# Arduino_Nano.net
KiCad netlist of a schematic drawn in Altium Designer
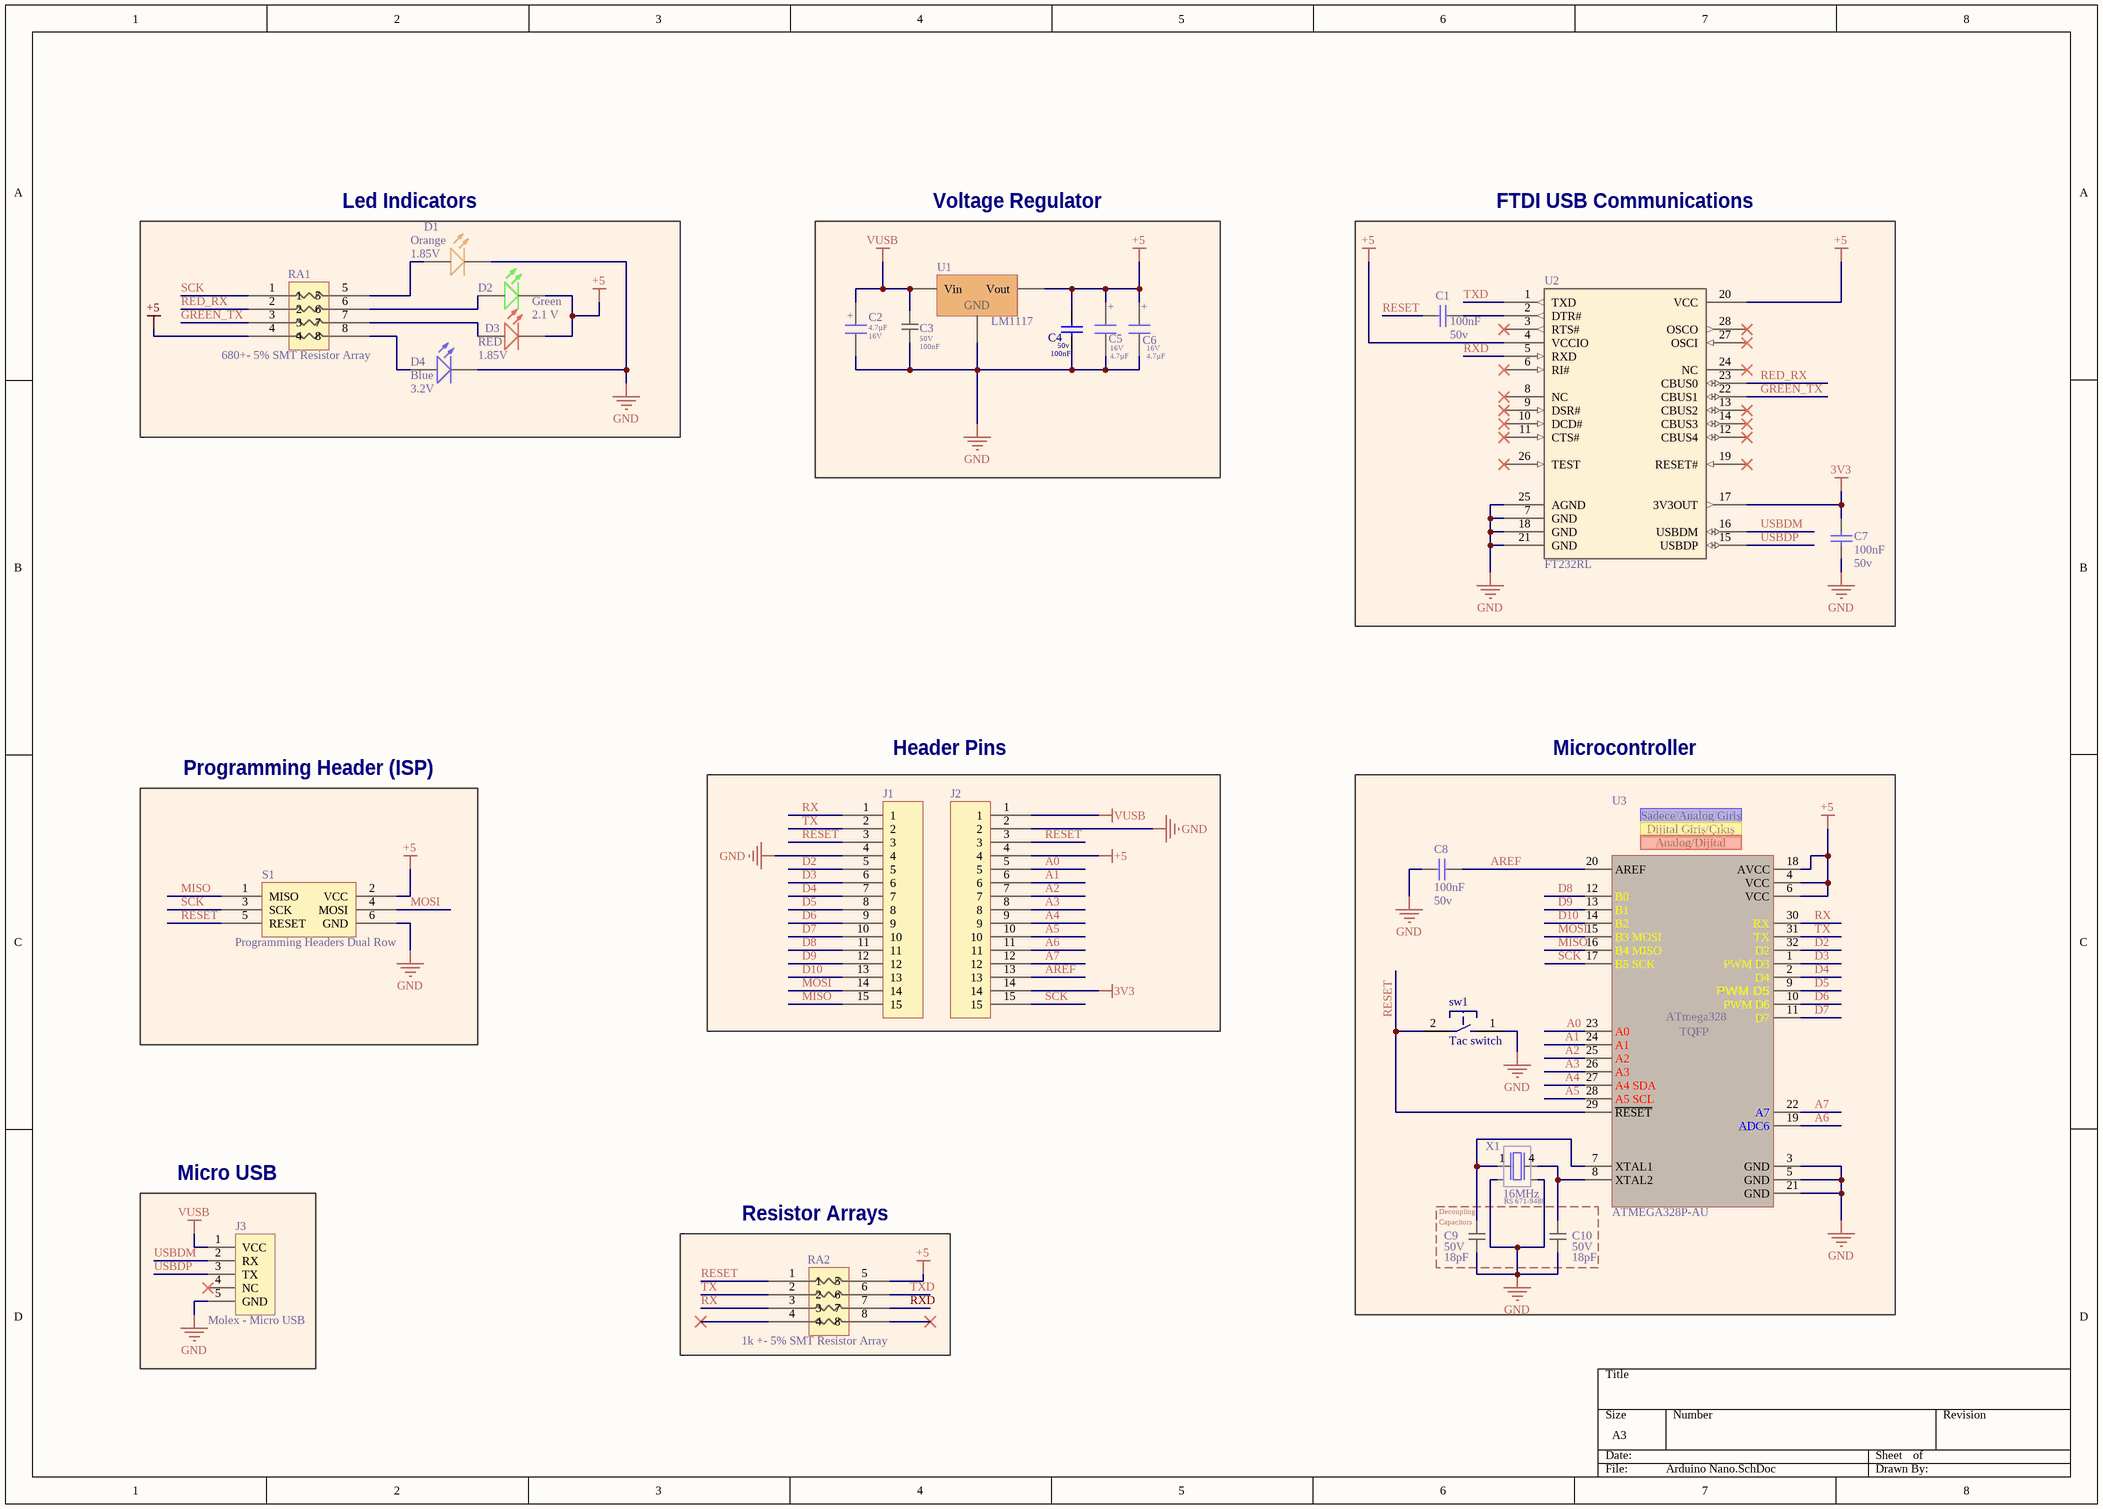
[diagram p0: Arduino Nano.SchDoc]

(export (version "E")
  (design (tool "Eeschema 10.0.6"))
  (components
    (comp (ref "C1")
      (value "100nF")
      (footprint "MY_0805")
      (description "None polar capacitor")
      (fields (field (name "ASID PART NUMBER") "C-AS") (field (name "VOLTE") "50v"))
      (libsource (lib "Kütüphanem") (part "Cap ceramic"))
    )
    (comp (ref "C2")
      (value "4.7µF")
      (footprint "CASE A - 3216X18")
      (description "Capacitor,tantalum,SMT,16V,4.7uF,10%,A-case")
      (fields
        (field (name "TOLERANCE") "10%")
        (field (name "VOLTAGE") "16V")
        (field (name "Comment") "Capacitor SMT Tantalum")
        (field (name "PUBLISHER") "DPSS")
      )
      (libsource (lib "Kütüphanem") (part "4.7µF Tant RS 496-3545"))
    )
    (comp (ref "C3")
      (value "100nF Ceramic Multilayer Capacitor_1")
      (footprint "CAPCP2012X09N")
      (description "AVX 0805 Standard 100nF Ceramic Multilayer Capacitor, 50 V dc X7R Dielectric ±10% SMD")
      (fields
        (field (name "MANUFACTURER") "AVX")
        (field (name "VOLTAGE") "50V")
        (field (name "CAPACITANCE") "100nF")
        (field (name "CREATOR") "Ritesh Kanjee")
      )
      (libsource (lib "Kütüphanem") (part "100nF Ceramic Multilayer Capacitor_1"))
    )
    (comp (ref "C4")
      (value "100nF")
      (footprint "MY_0805")
      (description "None polar capacitor")
      (fields (field (name "ASID PART NUMBER") "C-AS") (field (name "VOLTE") "50v"))
      (libsource (lib "Kütüphanem") (part "Cap ceramic"))
    )
    (comp (ref "C5")
      (value "4.7µF")
      (footprint "CASE A - 3216X18")
      (description "Capacitor,tantalum,SMT,16V,4.7uF,10%,A-case")
      (fields
        (field (name "TOLERANCE") "10%")
        (field (name "VOLTAGE") "16V")
        (field (name "Comment") "Capacitor SMT Tantalum")
        (field (name "PUBLISHER") "DPSS")
      )
      (libsource (lib "Kütüphanem") (part "4.7µF Tant RS 496-3545"))
    )
    (comp (ref "C6")
      (value "4.7µF")
      (footprint "CASE A - 3216X18")
      (description "Capacitor,tantalum,SMT,16V,4.7uF,10%,A-case")
      (fields
        (field (name "TOLERANCE") "10%")
        (field (name "VOLTAGE") "16V")
        (field (name "Comment") "Capacitor SMT Tantalum")
        (field (name "PUBLISHER") "DPSS")
      )
      (libsource (lib "Kütüphanem") (part "4.7µF Tant RS 496-3545"))
    )
    (comp (ref "C7")
      (value "100nF")
      (footprint "MY_0805")
      (description "None polar capacitor")
      (fields (field (name "ASID PART NUMBER") "C-AS") (field (name "VOLTE") "50v"))
      (libsource (lib "Kütüphanem") (part "Cap ceramic"))
    )
    (comp (ref "C8")
      (value "100nF")
      (footprint "MY_0805")
      (description "None polar capacitor")
      (fields (field (name "ASID PART NUMBER") "C-AS") (field (name "VOLTE") "50v"))
      (libsource (lib "Kütüphanem") (part "Cap ceramic"))
    )
    (comp (ref "C9")
      (value "C0805C180J5GACTU")
      (footprint "CAPCP2012X09N")
      (description "18pF Ceramic Multilayer Capacitor, 50 V dc C0G Dielectric ±5% SMD")
      (fields
        (field (name "MANUFACTURER") "Kemet")
        (field (name "VOLTAGE") "50V")
        (field (name "CAPACITANCE") "18pF")
        (field (name "CREATOR") "Ayberk Özkan")
      )
      (libsource (lib "Kütüphanem") (part "18pF Ceramic Multilayer Capacitor, 50 V dc C0G Dielectric ±5% SMD"))
    )
    (comp (ref "C10")
      (value "C0805C180J5GACTU")
      (footprint "CAPCP2012X09N")
      (description "18pF Ceramic Multilayer Capacitor, 50 V dc C0G Dielectric ±5% SMD")
      (fields
        (field (name "MANUFACTURER") "Kemet")
        (field (name "VOLTAGE") "50V")
        (field (name "CAPACITANCE") "18pF")
        (field (name "CREATOR") "Ayberk Özkan")
      )
      (libsource (lib "Kütüphanem") (part "18pF Ceramic Multilayer Capacitor, 50 V dc C0G Dielectric ±5% SMD"))
    )
    (comp (ref "D1")
      (value "Kingbright Orange LED, 200 mcd 120 ° 0805")
      (footprint "LED1913X12NYEL/ORANGE")
      (fields
        (field (name "MANUFACTURER") "KingBright")
        (field (name "MANUFACTURER PART NO.") "KP-2012SEC")
        (field (name "COLOR") "Orange")
        (field (name "FORWARD VOLTAGE") "1.85V")
        (field (name "CREATOR") "Ayberk Özkan")
      )
      (libsource (lib "Kütüphanem") (part "Kingbright Orange LED, 200 mcd 120 ° 0805"))
    )
    (comp (ref "D2")
      (value "Kingbright Green LED, 70 mcd 120 ° 0805")
      (footprint "LED1913X12NGREEN")
      (fields
        (field (name "MANUFACTURER") "KingBright")
        (field (name "MANUFACTURER PART NO.") "KP-2012MGC")
        (field (name "COLOR") "Green")
        (field (name "FORWARD VOLTAGE") "2.1 V")
        (field (name "CREATOR") "Ayberk Özkan")
      )
      (libsource (lib "Kütüphanem") (part "Kingbright Green LED, 70 mcd 120 ° 0805"))
    )
    (comp (ref "D3")
      (value "Kingbright Red LED, 100 mcd 120 ° 0805")
      (footprint "LED1913X12NRED")
      (fields
        (field (name "MANUFACTURER") "KingBright")
        (field (name "MANUFACTURER PART NO.") "KP-2012SRC-PRV")
        (field (name "COLOR") "RED")
        (field (name "FORWARD VOLTAGE") "1.85V")
        (field (name "CREATOR") "Ayberk Özkan")
      )
      (libsource (lib "Kütüphanem") (part "Kingbright Red LED, 100 mcd 120 ° 0805"))
    )
    (comp (ref "D4")
      (value "Kingbright Blue LED, 60 mcd 120 ° 0805")
      (footprint "LED1913X12NBLUE")
      (fields
        (field (name "MANUFACTURER") "KingBright")
        (field (name "MANUFACTURER PART NO.") "KP-2012PBC-A")
        (field (name "COLOR") "Blue")
        (field (name "FORWARD VOLTAGE") "3.2V")
        (field (name "CREATOR") "Ayberk Özkan")
      )
      (libsource (lib "Kütüphanem") (part "Kingbright Blue LED, 60 mcd 120 ° 0805"))
    )
    (comp (ref "J1")
      (value "connector;str header;single row;.1 cont centers;.095 tail;gold or gtx;36 contact")
      (footprint "Header")
      (fields
        (field (name "MANUFACTURER") "FCI")
        (field (name "MANUFACTURER PART NO.") "68000-236HLF")
        (field (name "CREATED BY") "Ayberk Özkan")
      )
      (libsource (lib "") (part "Single row; PCB headers_1"))
    )
    (comp (ref "J2")
      (value "connector;str header;single row;.1 cont centers;.095 tail;gold or gtx;36 contact")
      (footprint "Header")
      (fields
        (field (name "MANUFACTURER") "FCI")
        (field (name "MANUFACTURER PART NO.") "68000-236HLF")
        (field (name "CREATED BY") "Ayberk Özkan")
      )
      (libsource (lib "Kütüphanem") (part "Single row; PCB headers"))
    )
    (comp (ref "J3")
      (value "Molex - Micro USB")
      (footprint "MOLEX_1050170001")
      (description "Molex USB Connector, SMT, Socket B, Solder, Right Angle")
      (libsource (lib "Kütüphanem") (part "Molex - Micro USB Connector 30V, 1.8A"))
    )
    (comp (ref "RA1")
      (value "680+- 5% SMT Resistor Array")
      (footprint "1206 RA")
      (description "680 +- 5% SMT Resistor Array 4 Res 1206")
      (fields
        (field (name "MANUFACTURER") "Bourns")
        (field (name "MANUFACTURER PART NO.") "CAY16-681J4LF")
        (field (name "CREATOR") "Ayberk Özkan")
      )
      (libsource (lib "Kütüphanem") (part "680 +- 5% SMT Resistor Array 4 Res 1206"))
    )
    (comp (ref "RA2")
      (value "1k +- 5% SMT Resistor Array")
      (footprint "1206 RA")
      (description "1k +- 5% SMT Resistor Array 4 Res")
      (fields
        (field (name "MANUFACTURER") "Bourns")
        (field (name "MANUFACTURER PART NO.") "CAY16-102J4LF")
        (field (name "CREATOR") "Ayberk Özkan")
      )
      (libsource (lib "Kütüphanem") (part "1k +- 5% SMT Resistor Array"))
    )
    (comp (ref "S1")
      (value "Programming Headers Dual Row")
      (footprint "ISP HEADER")
      (libsource (lib "Kütüphanem") (part "Programming ISP, Programming Headers Dual Row"))
    )
    (comp (ref "sw1")
      (value "Tac switch")
      (footprint "MY_PB-SMD")
      (description "small tac switch")
      (fields (field (name "ASID PART NUMBER") "Tac switch-AS"))
      (libsource (lib "Kütüphanem") (part "Tac switch_1"))
    )
    (comp (ref "U1")
      (value "LM1117")
      (footprint "MY_SOT223")
      (description "Low Drop Voltage Reg")
      (fields (field (name "ASID PART NUMBER") "LM1117-AS"))
      (libsource (lib "Kütüphanem") (part "LM1117"))
    )
    (comp (ref "U2")
      (value "FT232RL")
      (footprint "SSOP-28-FT232RL")
      (description "USB Bridge, USB to UART USB 2.0 UART Interface 28-SSOP")
      (libsource (lib "Kütüphanem") (part "FT232RL"))
    )
    (comp (ref "U3")
      (value "ATMEGA328P-AU")
      (footprint "TQFP80P900X900X120-32N")
      (description "ATmega48A/PA/88A/PA/168A/PA/328/P")
      (fields (field (name "CREATED BY") "Ayberk"))
      (libsource (lib "Kütüphanem") (part "AtmelMicrocontroller"))
    )
    (comp (ref "X1")
      (value "16MHz")
      (footprint "Aker S5C Crystal")
      (description "Aker S5C SMT Crystal")
      (fields
        (field (name "MANUFACTURER") "Aker")
        (field (name "MANUFACTURER PART #") "C5S-16.000-12-3030-X")
        (field (name "RS") "RS 671-9488")
        (field (name "CREATOR") "Ayberk Özkan")
      )
      (libsource (lib "Kütüphanem") (part "Aker  C5S-16.000-12-3030-X"))
    )
  )
  (nets
    (net (code "1") (name "+5") (class "Default")
      (node (ref "C4") (pin "2") (pinfunction "2_2") (pintype "passive"))
      (node (ref "C5") (pin "1") (pinfunction "1_1") (pintype "passive"))
      (node (ref "C6") (pin "1") (pinfunction "1_1") (pintype "passive"))
      (node (ref "D2") (pin "2") (pinfunction "K_2") (pintype "passive"))
      (node (ref "D3") (pin "2") (pinfunction "K_2") (pintype "passive"))
      (node (ref "J2") (pin "4") (pinfunction "4_4") (pintype "passive"))
      (node (ref "RA1") (pin "4") (pinfunction "4_4") (pintype "passive"))
      (node (ref "RA2") (pin "5") (pinfunction "5_5") (pintype "passive"))
      (node (ref "S1") (pin "2") (pinfunction "VCC_2") (pintype "passive"))
      (node (ref "U1") (pin "2") (pinfunction "Vout_2") (pintype "passive"))
      (node (ref "U2") (pin "20") (pinfunction "VCC_20") (pintype "power_in"))
      (node (ref "U2") (pin "4") (pinfunction "VCCIO_4") (pintype "power_in"))
      (node (ref "U3") (pin "18") (pinfunction "AVCC_18") (pintype "passive"))
      (node (ref "U3") (pin "4") (pinfunction "VCC_4") (pintype "passive"))
      (node (ref "U3") (pin "6") (pinfunction "VCC_6") (pintype "passive"))
    )
    (net (code "2") (name "/A0") (class "Default")
      (node (ref "J2") (pin "5") (pinfunction "5_5") (pintype "passive"))
      (node (ref "U3") (pin "23") (pinfunction "A0_23") (pintype "passive"))
    )
    (net (code "3") (name "/A1") (class "Default")
      (node (ref "J2") (pin "6") (pinfunction "6_6") (pintype "passive"))
      (node (ref "U3") (pin "24") (pinfunction "A1_24") (pintype "passive"))
    )
    (net (code "4") (name "/A2") (class "Default")
      (node (ref "J2") (pin "7") (pinfunction "7_7") (pintype "passive"))
      (node (ref "U3") (pin "25") (pinfunction "A2_25") (pintype "passive"))
    )
    (net (code "5") (name "/A3") (class "Default")
      (node (ref "J2") (pin "8") (pinfunction "8_8") (pintype "passive"))
      (node (ref "U3") (pin "26") (pinfunction "A3_26") (pintype "passive"))
    )
    (net (code "6") (name "/A4") (class "Default")
      (node (ref "J2") (pin "9") (pinfunction "9_9") (pintype "passive"))
      (node (ref "U3") (pin "27") (pinfunction "A4_SDA_27") (pintype "passive"))
    )
    (net (code "7") (name "/A5") (class "Default")
      (node (ref "J2") (pin "10") (pinfunction "10_10") (pintype "passive"))
      (node (ref "U3") (pin "28") (pinfunction "A5_SCL_28") (pintype "passive"))
    )
    (net (code "8") (name "/A6") (class "Default")
      (node (ref "J2") (pin "11") (pinfunction "11_11") (pintype "passive"))
      (node (ref "U3") (pin "19") (pinfunction "ADC6_19") (pintype "passive"))
    )
    (net (code "9") (name "/A7") (class "Default")
      (node (ref "J2") (pin "12") (pinfunction "12_12") (pintype "passive"))
      (node (ref "U3") (pin "22") (pinfunction "A7_22") (pintype "passive"))
    )
    (net (code "10") (name "/AREF") (class "Default")
      (node (ref "C8") (pin "2") (pinfunction "2_2") (pintype "passive"))
      (node (ref "J2") (pin "13") (pinfunction "13_13") (pintype "passive"))
      (node (ref "U3") (pin "20") (pinfunction "AREF_20") (pintype "passive"))
    )
    (net (code "11") (name "/D2") (class "Default")
      (node (ref "J1") (pin "5") (pinfunction "5_5") (pintype "passive"))
      (node (ref "U3") (pin "32") (pinfunction "D2_32") (pintype "passive"))
    )
    (net (code "12") (name "/D3") (class "Default")
      (node (ref "J1") (pin "6") (pinfunction "6_6") (pintype "passive"))
      (node (ref "U3") (pin "1") (pinfunction "PWM_D3_1") (pintype "passive"))
    )
    (net (code "13") (name "/D4") (class "Default")
      (node (ref "J1") (pin "7") (pinfunction "7_7") (pintype "passive"))
      (node (ref "U3") (pin "2") (pinfunction "D4_2") (pintype "passive"))
    )
    (net (code "14") (name "/D5") (class "Default")
      (node (ref "J1") (pin "8") (pinfunction "8_8") (pintype "passive"))
      (node (ref "U3") (pin "9") (pinfunction "PWM_D5_9") (pintype "passive"))
    )
    (net (code "15") (name "/D6") (class "Default")
      (node (ref "J1") (pin "9") (pinfunction "9_9") (pintype "passive"))
      (node (ref "U3") (pin "10") (pinfunction "PWM_D6_10") (pintype "passive"))
    )
    (net (code "16") (name "/D7") (class "Default")
      (node (ref "J1") (pin "10") (pinfunction "10_10") (pintype "passive"))
      (node (ref "U3") (pin "11") (pinfunction "D7_11") (pintype "passive"))
    )
    (net (code "17") (name "/D8") (class "Default")
      (node (ref "J1") (pin "11") (pinfunction "11_11") (pintype "passive"))
      (node (ref "U3") (pin "12") (pinfunction "B0_12") (pintype "passive"))
    )
    (net (code "18") (name "/D9") (class "Default")
      (node (ref "J1") (pin "12") (pinfunction "12_12") (pintype "passive"))
      (node (ref "U3") (pin "13") (pinfunction "B1_13") (pintype "passive"))
    )
    (net (code "19") (name "/D10") (class "Default")
      (node (ref "J1") (pin "13") (pinfunction "13_13") (pintype "passive"))
      (node (ref "U3") (pin "14") (pinfunction "B2_14") (pintype "passive"))
    )
    (net (code "20") (name "/GREEN_TX") (class "Default")
      (node (ref "RA1") (pin "3") (pinfunction "3_3") (pintype "passive"))
      (node (ref "U2") (pin "22") (pinfunction "CBUS1_22") (pintype "bidirectional"))
    )
    (net (code "21") (name "/MISO") (class "Default")
      (node (ref "J1") (pin "15") (pinfunction "15_15") (pintype "passive"))
      (node (ref "S1") (pin "1") (pinfunction "MISO_1") (pintype "passive"))
      (node (ref "U3") (pin "16") (pinfunction "B4_MISO_16") (pintype "passive"))
    )
    (net (code "22") (name "/MOSI") (class "Default")
      (node (ref "J1") (pin "14") (pinfunction "14_14") (pintype "passive"))
      (node (ref "S1") (pin "4") (pinfunction "MOSI_4") (pintype "passive"))
      (node (ref "U3") (pin "15") (pinfunction "B3_MOSI_15") (pintype "passive"))
    )
    (net (code "23") (name "/RED_RX") (class "Default")
      (node (ref "RA1") (pin "2") (pinfunction "2_2") (pintype "passive"))
      (node (ref "U2") (pin "23") (pinfunction "CBUS0_23") (pintype "bidirectional"))
    )
    (net (code "24") (name "/RESET") (class "Default")
      (node (ref "C1") (pin "1") (pinfunction "1_1") (pintype "passive"))
      (node (ref "J1") (pin "3") (pinfunction "3_3") (pintype "passive"))
      (node (ref "J2") (pin "3") (pinfunction "3_3") (pintype "passive"))
      (node (ref "RA2") (pin "1") (pinfunction "1_1") (pintype "passive"))
      (node (ref "S1") (pin "5") (pinfunction "RESET_5") (pintype "passive"))
      (node (ref "U3") (pin "29") (pinfunction "~{RESET}_29") (pintype "passive"))
      (node (ref "sw1") (pin "2") (pinfunction "2_2") (pintype "passive"))
    )
    (net (code "25") (name "/RX") (class "Default")
      (node (ref "J1") (pin "1") (pinfunction "1_1") (pintype "passive"))
      (node (ref "RA2") (pin "3") (pinfunction "3_3") (pintype "passive"))
      (node (ref "U3") (pin "30") (pinfunction "RX_30") (pintype "passive"))
    )
    (net (code "26") (name "/RXD") (class "Default")
      (node (ref "RA2") (pin "7") (pinfunction "7_7") (pintype "passive"))
      (node (ref "U2") (pin "5") (pinfunction "RXD_5") (pintype "input"))
    )
    (net (code "27") (name "/SCK") (class "Default")
      (node (ref "J2") (pin "15") (pinfunction "15_15") (pintype "passive"))
      (node (ref "RA1") (pin "1") (pinfunction "1_1") (pintype "passive"))
      (node (ref "S1") (pin "3") (pinfunction "SCK_3") (pintype "passive"))
      (node (ref "U3") (pin "17") (pinfunction "B5_SCK_17") (pintype "passive"))
    )
    (net (code "28") (name "/TX") (class "Default")
      (node (ref "J1") (pin "2") (pinfunction "2_2") (pintype "passive"))
      (node (ref "RA2") (pin "2") (pinfunction "2_2") (pintype "passive"))
      (node (ref "U3") (pin "31") (pinfunction "TX_31") (pintype "passive"))
    )
    (net (code "29") (name "/TXD") (class "Default")
      (node (ref "RA2") (pin "6") (pinfunction "6_6") (pintype "passive"))
      (node (ref "U2") (pin "1") (pinfunction "TXD_1") (pintype "output"))
    )
    (net (code "30") (name "/USBDM") (class "Default")
      (node (ref "J3") (pin "2") (pinfunction "RX_2") (pintype "passive"))
      (node (ref "U2") (pin "16") (pinfunction "USBDM_16") (pintype "bidirectional"))
    )
    (net (code "31") (name "/USBDP") (class "Default")
      (node (ref "J3") (pin "3") (pinfunction "TX_3") (pintype "passive"))
      (node (ref "U2") (pin "15") (pinfunction "USBDP_15") (pintype "bidirectional"))
    )
    (net (code "32") (name "3V3") (class "Default")
      (node (ref "C7") (pin "2") (pinfunction "2_2") (pintype "passive"))
      (node (ref "J2") (pin "14") (pinfunction "14_14") (pintype "passive"))
      (node (ref "U2") (pin "17") (pinfunction "3V3OUT_17") (pintype "output"))
    )
    (net (code "33") (name "GND") (class "Default")
      (node (ref "C10") (pin "1") (pinfunction "1_1") (pintype "passive"))
      (node (ref "C2") (pin "2") (pinfunction "2_2") (pintype "passive"))
      (node (ref "C3") (pin "1") (pinfunction "1_1") (pintype "passive"))
      (node (ref "C4") (pin "1") (pinfunction "1_1") (pintype "passive"))
      (node (ref "C5") (pin "2") (pinfunction "2_2") (pintype "passive"))
      (node (ref "C6") (pin "2") (pinfunction "2_2") (pintype "passive"))
      (node (ref "C7") (pin "1") (pinfunction "1_1") (pintype "passive"))
      (node (ref "C8") (pin "1") (pinfunction "1_1") (pintype "passive"))
      (node (ref "C9") (pin "1") (pinfunction "1_1") (pintype "passive"))
      (node (ref "D1") (pin "2") (pinfunction "K_2") (pintype "passive"))
      (node (ref "D4") (pin "2") (pinfunction "K_2") (pintype "passive"))
      (node (ref "J1") (pin "4") (pinfunction "4_4") (pintype "passive"))
      (node (ref "J2") (pin "2") (pinfunction "2_2") (pintype "passive"))
      (node (ref "J3") (pin "5") (pinfunction "GND_5") (pintype "passive"))
      (node (ref "S1") (pin "6") (pinfunction "GND_6") (pintype "passive"))
      (node (ref "U1") (pin "1") (pinfunction "GND_1") (pintype "passive"))
      (node (ref "U2") (pin "18") (pinfunction "GND_18") (pintype "passive"))
      (node (ref "U2") (pin "21") (pinfunction "GND_21") (pintype "passive"))
      (node (ref "U2") (pin "25") (pinfunction "AGND_25") (pintype "power_in"))
      (node (ref "U2") (pin "7") (pinfunction "GND_7") (pintype "passive"))
      (node (ref "U3") (pin "21") (pinfunction "GND_21") (pintype "passive"))
      (node (ref "U3") (pin "3") (pinfunction "GND_3") (pintype "passive"))
      (node (ref "U3") (pin "5") (pinfunction "GND_5") (pintype "passive"))
      (node (ref "X1") (pin "2") (pinfunction "Gnd_2") (pintype "power_in"))
      (node (ref "X1") (pin "3") (pinfunction "Gnd_3") (pintype "power_in"))
      (node (ref "sw1") (pin "1") (pinfunction "1_1") (pintype "passive"))
    )
    (net (code "34") (name "Net-(D1-A)") (class "Default")
      (node (ref "D1") (pin "1") (pinfunction "A_1") (pintype "passive"))
      (node (ref "RA1") (pin "5") (pinfunction "5_5") (pintype "passive"))
    )
    (net (code "35") (name "Net-(D2-A)") (class "Default")
      (node (ref "D2") (pin "1") (pinfunction "A_1") (pintype "passive"))
      (node (ref "RA1") (pin "6") (pinfunction "6_6") (pintype "passive"))
    )
    (net (code "36") (name "Net-(D3-A)") (class "Default")
      (node (ref "D3") (pin "1") (pinfunction "A_1") (pintype "passive"))
      (node (ref "RA1") (pin "7") (pinfunction "7_7") (pintype "passive"))
    )
    (net (code "37") (name "Net-(D4-A)") (class "Default")
      (node (ref "D4") (pin "1") (pinfunction "A_1") (pintype "passive"))
      (node (ref "RA1") (pin "8") (pinfunction "8_8") (pintype "passive"))
    )
    (net (code "38") (name "Net-(U2-DTR#)") (class "Default")
      (node (ref "C1") (pin "2") (pinfunction "2_2") (pintype "passive"))
      (node (ref "U2") (pin "2") (pinfunction "DTR#_2") (pintype "output"))
    )
    (net (code "39") (name "Net-(U3-XTAL1)") (class "Default")
      (node (ref "C9") (pin "2") (pinfunction "2_2") (pintype "passive"))
      (node (ref "U3") (pin "7") (pinfunction "XTAL1_7") (pintype "passive"))
      (node (ref "X1") (pin "1") (pinfunction "1_1") (pintype "passive"))
    )
    (net (code "40") (name "Net-(U3-XTAL2)") (class "Default")
      (node (ref "C10") (pin "2") (pinfunction "2_2") (pintype "passive"))
      (node (ref "U3") (pin "8") (pinfunction "XTAL2_8") (pintype "passive"))
      (node (ref "X1") (pin "4") (pinfunction "4_4") (pintype "passive"))
    )
    (net (code "41") (name "VUSB") (class "Default")
      (node (ref "C2") (pin "1") (pinfunction "1_1") (pintype "passive"))
      (node (ref "C3") (pin "2") (pinfunction "2_2") (pintype "passive"))
      (node (ref "J2") (pin "1") (pinfunction "1_1") (pintype "passive"))
      (node (ref "J3") (pin "1") (pinfunction "VCC_1") (pintype "passive"))
      (node (ref "U1") (pin "3") (pinfunction "Vin_3") (pintype "passive"))
    )
    (net (code "42") (name "unconnected-(J3-NC-Pad4)") (class "Default")
      (node (ref "J3") (pin "4") (pinfunction "NC_4") (pintype "passive+no_connect"))
    )
    (net (code "43") (name "unconnected-(RA2-Pad4)") (class "Default")
      (node (ref "RA2") (pin "4") (pinfunction "4_4") (pintype "passive+no_connect"))
    )
    (net (code "44") (name "unconnected-(RA2-Pad8)") (class "Default")
      (node (ref "RA2") (pin "8") (pinfunction "8_8") (pintype "passive+no_connect"))
    )
    (net (code "45") (name "unconnected-(U2-CBUS2-Pad13)") (class "Default")
      (node (ref "U2") (pin "13") (pinfunction "CBUS2_13") (pintype "bidirectional+no_connect"))
    )
    (net (code "46") (name "unconnected-(U2-CBUS3-Pad14)") (class "Default")
      (node (ref "U2") (pin "14") (pinfunction "CBUS3_14") (pintype "bidirectional+no_connect"))
    )
    (net (code "47") (name "unconnected-(U2-CBUS4-Pad12)") (class "Default")
      (node (ref "U2") (pin "12") (pinfunction "CBUS4_12") (pintype "bidirectional+no_connect"))
    )
    (net (code "48") (name "unconnected-(U2-CTS#-Pad11)") (class "Default")
      (node (ref "U2") (pin "11") (pinfunction "CTS#_11") (pintype "input+no_connect"))
    )
    (net (code "49") (name "unconnected-(U2-DCD#-Pad10)") (class "Default")
      (node (ref "U2") (pin "10") (pinfunction "DCD#_10") (pintype "input+no_connect"))
    )
    (net (code "50") (name "unconnected-(U2-DSR#-Pad9)") (class "Default")
      (node (ref "U2") (pin "9") (pinfunction "DSR#_9") (pintype "input+no_connect"))
    )
    (net (code "51") (name "unconnected-(U2-NC-Pad8)") (class "Default")
      (node (ref "U2") (pin "8") (pinfunction "NC_8") (pintype "passive+no_connect"))
    )
    (net (code "52") (name "unconnected-(U2-NC-Pad24)") (class "Default")
      (node (ref "U2") (pin "24") (pinfunction "NC_24") (pintype "passive+no_connect"))
    )
    (net (code "53") (name "unconnected-(U2-OSCI-Pad27)") (class "Default")
      (node (ref "U2") (pin "27") (pinfunction "OSCI_27") (pintype "input+no_connect"))
    )
    (net (code "54") (name "unconnected-(U2-OSCO-Pad28)") (class "Default")
      (node (ref "U2") (pin "28") (pinfunction "OSCO_28") (pintype "output+no_connect"))
    )
    (net (code "55") (name "unconnected-(U2-RESET#-Pad19)") (class "Default")
      (node (ref "U2") (pin "19") (pinfunction "RESET#_19") (pintype "input+no_connect"))
    )
    (net (code "56") (name "unconnected-(U2-RI#-Pad6)") (class "Default")
      (node (ref "U2") (pin "6") (pinfunction "RI#_6") (pintype "input+no_connect"))
    )
    (net (code "57") (name "unconnected-(U2-RTS#-Pad3)") (class "Default")
      (node (ref "U2") (pin "3") (pinfunction "RTS#_3") (pintype "output+no_connect"))
    )
    (net (code "58") (name "unconnected-(U2-TEST-Pad26)") (class "Default")
      (node (ref "U2") (pin "26") (pinfunction "TEST_26") (pintype "input+no_connect"))
    )
  )
)
